# Filter_Capacitors_-_Signal_IoT.net
KiCad netlist of a schematic drawn in Altium Designer
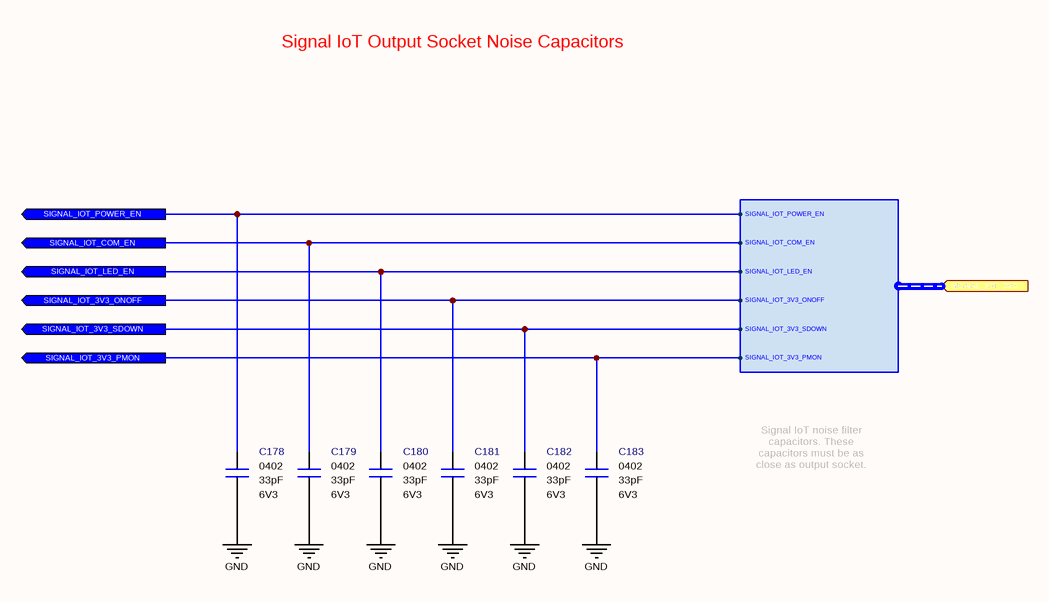
[diagram p0: Filter Capacitors - Signal IoT.SchDoc]

(export (version "E")
  (design (tool "Eeschema 10.0.6"))
  (components
    (comp (ref "C178")
      (value "33pF")
      (footprint "CAPACITOR_0402")
      (description "Capacitor - 33pF [0402] (Ceramic)")
      (fields
        (field (name "TOLERANCE") "10%")
        (field (name "CASE") "0402")
        (field (name "VOLTAGE") "6V3")
        (field (name "MANUFACTURER PART NUMBER") "C0402C330J9RACAUTO")
      )
      (libsource (lib "Ovoo_Library") (part "Capacitor - 33pF [0402-6V3]"))
    )
    (comp (ref "C179")
      (value "33pF")
      (footprint "CAPACITOR_0402")
      (description "Capacitor - 33pF [0402] (Ceramic)")
      (fields
        (field (name "TOLERANCE") "10%")
        (field (name "CASE") "0402")
        (field (name "VOLTAGE") "6V3")
        (field (name "MANUFACTURER PART NUMBER") "C0402C330J9RACAUTO")
      )
      (libsource (lib "Ovoo_Library") (part "Capacitor - 33pF [0402-6V3]"))
    )
    (comp (ref "C180")
      (value "33pF")
      (footprint "CAPACITOR_0402")
      (description "Capacitor - 33pF [0402] (Ceramic)")
      (fields
        (field (name "TOLERANCE") "10%")
        (field (name "CASE") "0402")
        (field (name "VOLTAGE") "6V3")
        (field (name "MANUFACTURER PART NUMBER") "C0402C330J9RACAUTO")
      )
      (libsource (lib "Ovoo_Library") (part "Capacitor - 33pF [0402-6V3]"))
    )
    (comp (ref "C181")
      (value "33pF")
      (footprint "CAPACITOR_0402")
      (description "Capacitor - 33pF [0402] (Ceramic)")
      (fields
        (field (name "TOLERANCE") "10%")
        (field (name "CASE") "0402")
        (field (name "VOLTAGE") "6V3")
        (field (name "MANUFACTURER PART NUMBER") "C0402C330J9RACAUTO")
      )
      (libsource (lib "Ovoo_Library") (part "Capacitor - 33pF [0402-6V3]"))
    )
    (comp (ref "C182")
      (value "33pF")
      (footprint "CAPACITOR_0402")
      (description "Capacitor - 33pF [0402] (Ceramic)")
      (fields
        (field (name "TOLERANCE") "10%")
        (field (name "CASE") "0402")
        (field (name "VOLTAGE") "6V3")
        (field (name "MANUFACTURER PART NUMBER") "C0402C330J9RACAUTO")
      )
      (libsource (lib "Ovoo_Library") (part "Capacitor - 33pF [0402-6V3]"))
    )
    (comp (ref "C183")
      (value "33pF")
      (footprint "CAPACITOR_0402")
      (description "Capacitor - 33pF [0402] (Ceramic)")
      (fields
        (field (name "TOLERANCE") "10%")
        (field (name "CASE") "0402")
        (field (name "VOLTAGE") "6V3")
        (field (name "MANUFACTURER PART NUMBER") "C0402C330J9RACAUTO")
      )
      (libsource (lib "Ovoo_Library") (part "Capacitor - 33pF [0402-6V3]"))
    )
  )
  (nets
    (net (code "2") (name "/SIGNAL_IOT_3V3_ONOFF") (class "Default")
      (node (ref "C181") (pin "2") (pinfunction "2_2") (pintype "passive"))
    )
    (net (code "3") (name "/SIGNAL_IOT_3V3_PMON") (class "Default")
      (node (ref "C183") (pin "2") (pinfunction "2_2") (pintype "passive"))
    )
    (net (code "4") (name "/SIGNAL_IOT_3V3_SDOWN") (class "Default")
      (node (ref "C182") (pin "2") (pinfunction "2_2") (pintype "passive"))
    )
    (net (code "5") (name "/SIGNAL_IOT_COM_EN") (class "Default")
      (node (ref "C179") (pin "2") (pinfunction "2_2") (pintype "passive"))
    )
    (net (code "6") (name "/SIGNAL_IOT_LED_EN") (class "Default")
      (node (ref "C180") (pin "2") (pinfunction "2_2") (pintype "passive"))
    )
    (net (code "7") (name "/SIGNAL_IOT_POWER_EN") (class "Default")
      (node (ref "C178") (pin "2") (pinfunction "2_2") (pintype "passive"))
    )
    (net (code "9") (name "GND") (class "Default")
      (node (ref "C178") (pin "1") (pinfunction "1_1") (pintype "passive"))
      (node (ref "C179") (pin "1") (pinfunction "1_1") (pintype "passive"))
      (node (ref "C180") (pin "1") (pinfunction "1_1") (pintype "passive"))
      (node (ref "C181") (pin "1") (pinfunction "1_1") (pintype "passive"))
      (node (ref "C182") (pin "1") (pinfunction "1_1") (pintype "passive"))
      (node (ref "C183") (pin "1") (pinfunction "1_1") (pintype "passive"))
    )
  )
)
